# plc-6u-rs485-router.net
KiCad netlist of a schematic drawn in EAGLE
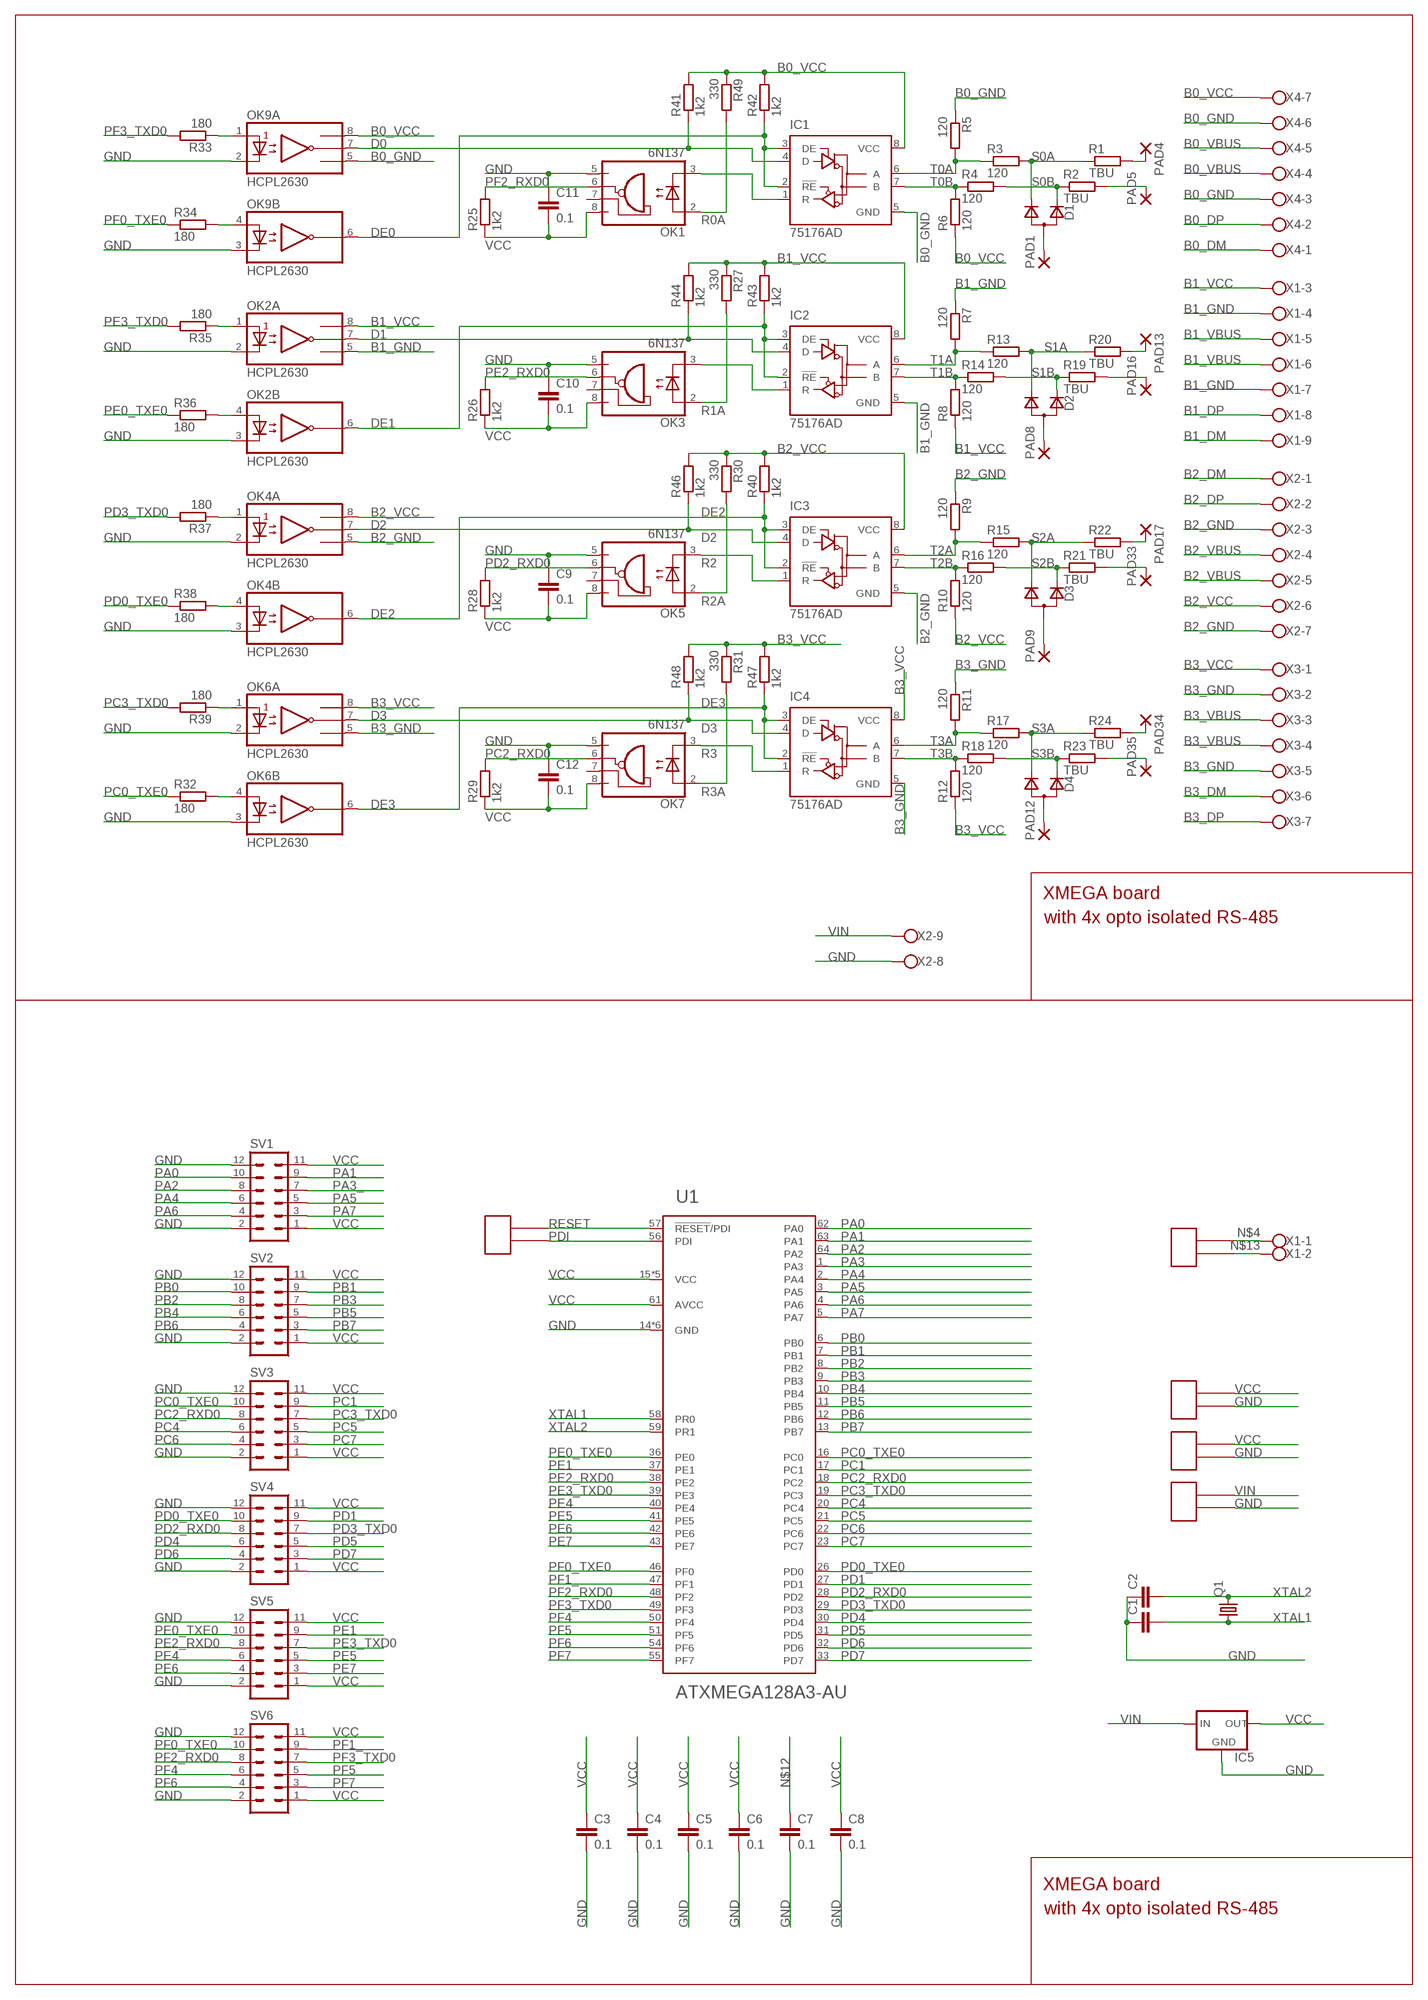
[diagram p0: schematic, sheet 1]

(export (version "E")
  (design (tool "Eeschema 10.0.6"))
  (components
    (comp (ref "C1")
      (value "C-EUC0805")
      (footprint "eagle-import:C0805")
      (libsource (lib "eagle-import") (part "C-EUC0805"))
    )
    (comp (ref "C2")
      (value "C-EUC0805")
      (footprint "eagle-import:C0805")
      (libsource (lib "eagle-import") (part "C-EUC0805"))
    )
    (comp (ref "C3")
      (value "0.1")
      (footprint "eagle-import:C0603")
      (libsource (lib "eagle-import") (part "C-EUC0603"))
    )
    (comp (ref "C4")
      (value "0.1")
      (footprint "eagle-import:C0603")
      (libsource (lib "eagle-import") (part "C-EUC0603"))
    )
    (comp (ref "C5")
      (value "0.1")
      (footprint "eagle-import:C0603")
      (libsource (lib "eagle-import") (part "C-EUC0603"))
    )
    (comp (ref "C6")
      (value "0.1")
      (footprint "eagle-import:C0603")
      (libsource (lib "eagle-import") (part "C-EUC0603"))
    )
    (comp (ref "C7")
      (value "0.1")
      (footprint "eagle-import:C0603")
      (libsource (lib "eagle-import") (part "C-EUC0603"))
    )
    (comp (ref "C8")
      (value "0.1")
      (footprint "eagle-import:C0603")
      (libsource (lib "eagle-import") (part "C-EUC0603"))
    )
    (comp (ref "C9")
      (value "0.1")
      (footprint "eagle-import:C1206")
      (libsource (lib "eagle-import") (part "C-EUC1206"))
    )
    (comp (ref "C10")
      (value "0.1")
      (footprint "eagle-import:C1206")
      (libsource (lib "eagle-import") (part "C-EUC1206"))
    )
    (comp (ref "C11")
      (value "0.1")
      (footprint "eagle-import:C1206")
      (libsource (lib "eagle-import") (part "C-EUC1206"))
    )
    (comp (ref "C12")
      (value "0.1")
      (footprint "eagle-import:C1206")
      (libsource (lib "eagle-import") (part "C-EUC1206"))
    )
    (comp (ref "D1")
      (value "D_2CSOT323")
      (footprint "eagle-import:SOT323")
      (libsource (lib "eagle-import") (part "D_2CSOT323"))
    )
    (comp (ref "D2")
      (value "D_2CSOT323")
      (footprint "eagle-import:SOT323")
      (fields (field (name "OC_FARNELL") "unknown") (field (name "OC_NEWARK") "unknown"))
      (libsource (lib "eagle-import") (part "D_2CSOT323"))
    )
    (comp (ref "D3")
      (value "D_2CSOT323")
      (footprint "eagle-import:SOT323")
      (fields (field (name "OC_FARNELL") "unknown") (field (name "OC_NEWARK") "unknown"))
      (libsource (lib "eagle-import") (part "D_2CSOT323"))
    )
    (comp (ref "D4")
      (value "D_2CSOT323")
      (footprint "eagle-import:SOT323")
      (fields (field (name "OC_FARNELL") "unknown") (field (name "OC_NEWARK") "unknown"))
      (libsource (lib "eagle-import") (part "D_2CSOT323"))
    )
    (comp (ref "IC1")
      (value "75176AD")
      (footprint "eagle-import:D_R-PDSO-G8")
      (libsource (lib "eagle-import") (part "75176AD"))
    )
    (comp (ref "IC2")
      (value "75176AD")
      (footprint "eagle-import:D_R-PDSO-G8")
      (libsource (lib "eagle-import") (part "75176AD"))
    )
    (comp (ref "IC3")
      (value "75176AD")
      (footprint "eagle-import:D_R-PDSO-G8")
      (libsource (lib "eagle-import") (part "75176AD"))
    )
    (comp (ref "IC4")
      (value "75176AD")
      (footprint "eagle-import:D_R-PDSO-G8")
      (libsource (lib "eagle-import") (part "75176AD"))
    )
    (comp (ref "IC5")
      (value "LM1117TO252")
      (footprint "eagle-import:TO252")
      (libsource (lib "eagle-import") (part "LM1117TO252"))
    )
    (comp (ref "OK1")
      (value "6N137")
      (footprint "eagle-import:DIL08")
      (libsource (lib "eagle-import") (part "6N137"))
    )
    (comp (ref "OK2")
      (value "HCPL2630")
      (footprint "eagle-import:DIL08")
      (fields (field (name "MF") "AGILENT TECHNOLOGIES") (field (name "MPN") "HCPL-2630-000E"))
      (libsource (lib "eagle-import") (part "HCPL2630"))
    )
    (comp (ref "OK3")
      (value "6N137")
      (footprint "eagle-import:DIL08")
      (libsource (lib "eagle-import") (part "6N137"))
    )
    (comp (ref "OK4")
      (value "HCPL2630")
      (footprint "eagle-import:DIL08")
      (fields (field (name "MF") "AGILENT TECHNOLOGIES") (field (name "MPN") "HCPL-2630-000E"))
      (libsource (lib "eagle-import") (part "HCPL2630"))
    )
    (comp (ref "OK5")
      (value "6N137")
      (footprint "eagle-import:DIL08")
      (libsource (lib "eagle-import") (part "6N137"))
    )
    (comp (ref "OK6")
      (value "HCPL2630")
      (footprint "eagle-import:DIL08")
      (fields (field (name "MF") "AGILENT TECHNOLOGIES") (field (name "MPN") "HCPL-2630-000E"))
      (libsource (lib "eagle-import") (part "HCPL2630"))
    )
    (comp (ref "OK7")
      (value "6N137")
      (footprint "eagle-import:DIL08")
      (libsource (lib "eagle-import") (part "6N137"))
    )
    (comp (ref "OK9")
      (value "HCPL2630")
      (footprint "eagle-import:DIL08")
      (fields (field (name "MF") "AGILENT TECHNOLOGIES") (field (name "MPN") "HCPL-2630-000E"))
      (libsource (lib "eagle-import") (part "HCPL2630"))
    )
    (comp (ref "PAD1")
      (value "2,54/0,8")
      (footprint "eagle-import:2,54_0,8")
      (libsource (lib "eagle-import") (part "2,54/0,8"))
    )
    (comp (ref "PAD4")
      (value "2,54/0,8")
      (footprint "eagle-import:2,54_0,8")
      (libsource (lib "eagle-import") (part "2,54/0,8"))
    )
    (comp (ref "PAD5")
      (value "2,54/0,8")
      (footprint "eagle-import:2,54_0,8")
      (libsource (lib "eagle-import") (part "2,54/0,8"))
    )
    (comp (ref "PAD8")
      (value "2,54/0,8")
      (footprint "eagle-import:2,54_0,8")
      (libsource (lib "eagle-import") (part "2,54/0,8"))
    )
    (comp (ref "PAD9")
      (value "2,54/0,8")
      (footprint "eagle-import:2,54_0,8")
      (libsource (lib "eagle-import") (part "2,54/0,8"))
    )
    (comp (ref "PAD12")
      (value "2,54/0,8")
      (footprint "eagle-import:2,54_0,8")
      (libsource (lib "eagle-import") (part "2,54/0,8"))
    )
    (comp (ref "PAD13")
      (value "2,54/0,8")
      (footprint "eagle-import:2,54_0,8")
      (libsource (lib "eagle-import") (part "2,54/0,8"))
    )
    (comp (ref "PAD16")
      (value "2,54/0,8")
      (footprint "eagle-import:2,54_0,8")
      (libsource (lib "eagle-import") (part "2,54/0,8"))
    )
    (comp (ref "PAD17")
      (value "2,54/0,8")
      (footprint "eagle-import:2,54_0,8")
      (libsource (lib "eagle-import") (part "2,54/0,8"))
    )
    (comp (ref "PAD33")
      (value "2,54/0,8")
      (footprint "eagle-import:2,54_0,8")
      (libsource (lib "eagle-import") (part "2,54/0,8"))
    )
    (comp (ref "PAD34")
      (value "2,54/0,8")
      (footprint "eagle-import:2,54_0,8")
      (libsource (lib "eagle-import") (part "2,54/0,8"))
    )
    (comp (ref "PAD35")
      (value "2,54/0,8")
      (footprint "eagle-import:2,54_0,8")
      (libsource (lib "eagle-import") (part "2,54/0,8"))
    )
    (comp (ref "Q1")
      (value "CRYSTALHC49S")
      (footprint "eagle-import:HC49_S")
      (libsource (lib "eagle-import") (part "CRYSTALHC49S"))
    )
    (comp (ref "R1")
      (value "TBU")
      (footprint "eagle-import:WSC2515")
      (libsource (lib "eagle-import") (part "R-EU_WSC2515"))
    )
    (comp (ref "R2")
      (value "TBU")
      (footprint "eagle-import:WSC2515")
      (libsource (lib "eagle-import") (part "R-EU_WSC2515"))
    )
    (comp (ref "R3")
      (value "120")
      (footprint "eagle-import:R0805")
      (libsource (lib "eagle-import") (part "R-EU_R0805"))
    )
    (comp (ref "R4")
      (value "120")
      (footprint "eagle-import:R0805")
      (libsource (lib "eagle-import") (part "R-EU_R0805"))
    )
    (comp (ref "R5")
      (value "120")
      (footprint "eagle-import:R0805")
      (libsource (lib "eagle-import") (part "R-EU_R0805"))
    )
    (comp (ref "R6")
      (value "120")
      (footprint "eagle-import:R0805")
      (libsource (lib "eagle-import") (part "R-EU_R0805"))
    )
    (comp (ref "R7")
      (value "120")
      (footprint "eagle-import:R0805")
      (libsource (lib "eagle-import") (part "R-EU_R0805"))
    )
    (comp (ref "R8")
      (value "120")
      (footprint "eagle-import:R0805")
      (libsource (lib "eagle-import") (part "R-EU_R0805"))
    )
    (comp (ref "R9")
      (value "120")
      (footprint "eagle-import:R0805")
      (libsource (lib "eagle-import") (part "R-EU_R0805"))
    )
    (comp (ref "R10")
      (value "120")
      (footprint "eagle-import:R0805")
      (libsource (lib "eagle-import") (part "R-EU_R0805"))
    )
    (comp (ref "R11")
      (value "120")
      (footprint "eagle-import:R0805")
      (libsource (lib "eagle-import") (part "R-EU_R0805"))
    )
    (comp (ref "R12")
      (value "120")
      (footprint "eagle-import:R0805")
      (libsource (lib "eagle-import") (part "R-EU_R0805"))
    )
    (comp (ref "R13")
      (value "120")
      (footprint "eagle-import:R0805")
      (libsource (lib "eagle-import") (part "R-EU_R0805"))
    )
    (comp (ref "R14")
      (value "120")
      (footprint "eagle-import:R0805")
      (libsource (lib "eagle-import") (part "R-EU_R0805"))
    )
    (comp (ref "R15")
      (value "120")
      (footprint "eagle-import:R0805")
      (libsource (lib "eagle-import") (part "R-EU_R0805"))
    )
    (comp (ref "R16")
      (value "120")
      (footprint "eagle-import:R0805")
      (libsource (lib "eagle-import") (part "R-EU_R0805"))
    )
    (comp (ref "R17")
      (value "120")
      (footprint "eagle-import:R0805")
      (libsource (lib "eagle-import") (part "R-EU_R0805"))
    )
    (comp (ref "R18")
      (value "120")
      (footprint "eagle-import:R0805")
      (libsource (lib "eagle-import") (part "R-EU_R0805"))
    )
    (comp (ref "R19")
      (value "TBU")
      (footprint "eagle-import:WSC2515")
      (libsource (lib "eagle-import") (part "R-EU_WSC2515"))
    )
    (comp (ref "R20")
      (value "TBU")
      (footprint "eagle-import:WSC2515")
      (libsource (lib "eagle-import") (part "R-EU_WSC2515"))
    )
    (comp (ref "R21")
      (value "TBU")
      (footprint "eagle-import:WSC2515")
      (libsource (lib "eagle-import") (part "R-EU_WSC2515"))
    )
    (comp (ref "R22")
      (value "TBU")
      (footprint "eagle-import:WSC2515")
      (libsource (lib "eagle-import") (part "R-EU_WSC2515"))
    )
    (comp (ref "R23")
      (value "TBU")
      (footprint "eagle-import:WSC2515")
      (libsource (lib "eagle-import") (part "R-EU_WSC2515"))
    )
    (comp (ref "R24")
      (value "TBU")
      (footprint "eagle-import:WSC2515")
      (libsource (lib "eagle-import") (part "R-EU_WSC2515"))
    )
    (comp (ref "R25")
      (value "1k2")
      (footprint "eagle-import:R0805")
      (libsource (lib "eagle-import") (part "R-EU_R0805"))
    )
    (comp (ref "R26")
      (value "1k2")
      (footprint "eagle-import:R0805")
      (libsource (lib "eagle-import") (part "R-EU_R0805"))
    )
    (comp (ref "R27")
      (value "330")
      (footprint "eagle-import:R0805")
      (libsource (lib "eagle-import") (part "R-EU_R0805"))
    )
    (comp (ref "R28")
      (value "1k2")
      (footprint "eagle-import:R0805")
      (libsource (lib "eagle-import") (part "R-EU_R0805"))
    )
    (comp (ref "R29")
      (value "1k2")
      (footprint "eagle-import:R0805")
      (libsource (lib "eagle-import") (part "R-EU_R0805"))
    )
    (comp (ref "R30")
      (value "330")
      (footprint "eagle-import:R0805")
      (libsource (lib "eagle-import") (part "R-EU_R0805"))
    )
    (comp (ref "R31")
      (value "330")
      (footprint "eagle-import:R0805")
      (libsource (lib "eagle-import") (part "R-EU_R0805"))
    )
    (comp (ref "R32")
      (value "180")
      (footprint "eagle-import:R1206")
      (libsource (lib "eagle-import") (part "R-EU_R1206"))
    )
    (comp (ref "R33")
      (value "180")
      (footprint "eagle-import:R0805")
      (libsource (lib "eagle-import") (part "R-EU_R0805"))
    )
    (comp (ref "R34")
      (value "180")
      (footprint "eagle-import:R1206")
      (libsource (lib "eagle-import") (part "R-EU_R1206"))
    )
    (comp (ref "R35")
      (value "180")
      (footprint "eagle-import:R0805")
      (libsource (lib "eagle-import") (part "R-EU_R0805"))
    )
    (comp (ref "R36")
      (value "180")
      (footprint "eagle-import:R1206")
      (libsource (lib "eagle-import") (part "R-EU_R1206"))
    )
    (comp (ref "R37")
      (value "180")
      (footprint "eagle-import:R0805")
      (libsource (lib "eagle-import") (part "R-EU_R0805"))
    )
    (comp (ref "R38")
      (value "180")
      (footprint "eagle-import:R1206")
      (libsource (lib "eagle-import") (part "R-EU_R1206"))
    )
    (comp (ref "R39")
      (value "180")
      (footprint "eagle-import:R0805")
      (libsource (lib "eagle-import") (part "R-EU_R0805"))
    )
    (comp (ref "R40")
      (value "1k2")
      (footprint "eagle-import:0207_10")
      (libsource (lib "eagle-import") (part "resistor_R-EU_0207/10"))
    )
    (comp (ref "R41")
      (value "1k2")
      (footprint "eagle-import:0207_10")
      (libsource (lib "eagle-import") (part "resistor_R-EU_0207/10"))
    )
    (comp (ref "R42")
      (value "1k2")
      (footprint "eagle-import:0207_10")
      (libsource (lib "eagle-import") (part "resistor_R-EU_0207/10"))
    )
    (comp (ref "R43")
      (value "1k2")
      (footprint "eagle-import:R0805")
      (libsource (lib "eagle-import") (part "R-EU_R0805"))
    )
    (comp (ref "R44")
      (value "1k2")
      (footprint "eagle-import:R0805")
      (libsource (lib "eagle-import") (part "R-EU_R0805"))
    )
    (comp (ref "R46")
      (value "1k2")
      (footprint "eagle-import:0207_10")
      (libsource (lib "eagle-import") (part "resistor_R-EU_0207/10"))
    )
    (comp (ref "R47")
      (value "1k2")
      (footprint "eagle-import:R0805")
      (libsource (lib "eagle-import") (part "R-EU_R0805"))
    )
    (comp (ref "R48")
      (value "1k2")
      (footprint "eagle-import:R0805")
      (libsource (lib "eagle-import") (part "R-EU_R0805"))
    )
    (comp (ref "R49")
      (value "330")
      (footprint "eagle-import:R0805")
      (libsource (lib "eagle-import") (part "R-EU_R0805"))
    )
    (comp (ref "SV1")
      (value "MA06-2")
      (footprint "eagle-import:MA06-2")
      (libsource (lib "eagle-import") (part "MA06-2"))
    )
    (comp (ref "SV2")
      (value "MA06-2")
      (footprint "eagle-import:MA06-2")
      (libsource (lib "eagle-import") (part "MA06-2"))
    )
    (comp (ref "SV3")
      (value "MA06-2")
      (footprint "eagle-import:MA06-2")
      (libsource (lib "eagle-import") (part "MA06-2"))
    )
    (comp (ref "SV4")
      (value "MA06-2")
      (footprint "eagle-import:MA06-2")
      (libsource (lib "eagle-import") (part "MA06-2"))
    )
    (comp (ref "SV5")
      (value "MA06-2")
      (footprint "eagle-import:MA06-2")
      (libsource (lib "eagle-import") (part "MA06-2"))
    )
    (comp (ref "SV6")
      (value "MA06-2")
      (footprint "eagle-import:MA06-2")
      (libsource (lib "eagle-import") (part "MA06-2"))
    )
    (comp (ref "U$1")
      (value "MA02-1")
      (footprint "eagle-import:MA02-1")
      (libsource (lib "eagle-import") (part "MA02-1"))
    )
    (comp (ref "U$2")
      (value "MA02-1")
      (footprint "eagle-import:MA02-1")
      (libsource (lib "eagle-import") (part "MA02-1"))
    )
    (comp (ref "U$3")
      (value "MA02-1")
      (footprint "eagle-import:MA02-1")
      (libsource (lib "eagle-import") (part "MA02-1"))
    )
    (comp (ref "U$4")
      (value "MA02-1")
      (footprint "eagle-import:MA02-1")
      (libsource (lib "eagle-import") (part "MA02-1"))
    )
    (comp (ref "U$5")
      (value "MA02-1")
      (footprint "eagle-import:MA02-1")
      (libsource (lib "eagle-import") (part "MA02-1"))
    )
    (comp (ref "U1")
      (value "ATXMEGA128A3-AU")
      (footprint "eagle-import:TQFP-64A-64")
      (libsource (lib "eagle-import") (part "ATXMEGA128A3-AU"))
    )
    (comp (ref "X1")
      (value "W237-09P")
      (footprint "eagle-import:W237-9P")
      (libsource (lib "eagle-import") (part "W237-09P"))
    )
    (comp (ref "X2")
      (value "W237-09P")
      (footprint "eagle-import:W237-9P")
      (libsource (lib "eagle-import") (part "W237-09P"))
    )
    (comp (ref "X3")
      (value "W237-07P")
      (footprint "eagle-import:W237-7P")
      (libsource (lib "eagle-import") (part "W237-07P"))
    )
    (comp (ref "X4")
      (value "W237-07P")
      (footprint "eagle-import:W237-7P")
      (libsource (lib "eagle-import") (part "W237-07P"))
    )
  )
  (nets
    (net (code "1") (name "/B0_DM") (class "Default")
      (node (ref "PAD4") (pin "1") (pinfunction "P_1") (pintype "passive"))
      (node (ref "R1") (pin "2") (pinfunction "2_2") (pintype "passive"))
      (node (ref "X4") (pin "1") (pinfunction "KL_1") (pintype "passive"))
    )
    (net (code "2") (name "/B0_DP") (class "Default")
      (node (ref "PAD5") (pin "1") (pinfunction "P_1") (pintype "passive"))
      (node (ref "R2") (pin "2") (pinfunction "2_2") (pintype "passive"))
      (node (ref "X4") (pin "2") (pinfunction "KL_2") (pintype "passive"))
    )
    (net (code "3") (name "/B0_GND") (class "Default")
      (node (ref "D1") (pin "1") (pinfunction "A_1") (pintype "passive"))
      (node (ref "IC1") (pin "5") (pinfunction "GND_5") (pintype "power_in"))
      (node (ref "OK9") (pin "5") (pinfunction "GND_5") (pintype "passive"))
      (node (ref "PAD1") (pin "1") (pinfunction "P_1") (pintype "passive"))
      (node (ref "R5") (pin "1") (pinfunction "1_1") (pintype "passive"))
      (node (ref "X4") (pin "3") (pinfunction "KL_3") (pintype "passive"))
      (node (ref "X4") (pin "6") (pinfunction "KL_6") (pintype "passive"))
    )
    (net (code "4") (name "/B0_VBUS") (class "Default")
      (node (ref "X4") (pin "4") (pinfunction "KL_4") (pintype "passive"))
      (node (ref "X4") (pin "5") (pinfunction "KL_5") (pintype "passive"))
    )
    (net (code "5") (name "/B0_VCC") (class "Default")
      (node (ref "IC1") (pin "8") (pinfunction "VCC_8") (pintype "power_in"))
      (node (ref "OK9") (pin "8") (pinfunction "VCC_8") (pintype "passive"))
      (node (ref "R41") (pin "2") (pinfunction "2_2") (pintype "passive"))
      (node (ref "R42") (pin "2") (pinfunction "2_2") (pintype "passive"))
      (node (ref "R49") (pin "1") (pinfunction "1_1") (pintype "passive"))
      (node (ref "R6") (pin "1") (pinfunction "1_1") (pintype "passive"))
      (node (ref "X4") (pin "7") (pinfunction "KL_7") (pintype "passive"))
    )
    (net (code "6") (name "/B1_DM") (class "Default")
      (node (ref "PAD16") (pin "1") (pinfunction "P_1") (pintype "passive"))
      (node (ref "R19") (pin "2") (pinfunction "2_2") (pintype "passive"))
      (node (ref "X1") (pin "9") (pinfunction "KL_9") (pintype "passive"))
    )
    (net (code "7") (name "/B1_DP") (class "Default")
      (node (ref "PAD13") (pin "1") (pinfunction "P_1") (pintype "passive"))
      (node (ref "R20") (pin "2") (pinfunction "2_2") (pintype "passive"))
      (node (ref "X1") (pin "8") (pinfunction "KL_8") (pintype "passive"))
    )
    (net (code "8") (name "/B1_GND") (class "Default")
      (node (ref "D2") (pin "1") (pinfunction "A_1") (pintype "passive"))
      (node (ref "IC2") (pin "5") (pinfunction "GND_5") (pintype "power_in"))
      (node (ref "OK2") (pin "5") (pinfunction "GND_5") (pintype "passive"))
      (node (ref "PAD8") (pin "1") (pinfunction "P_1") (pintype "passive"))
      (node (ref "R7") (pin "1") (pinfunction "1_1") (pintype "passive"))
      (node (ref "X1") (pin "4") (pinfunction "KL_4") (pintype "passive"))
      (node (ref "X1") (pin "7") (pinfunction "KL_7") (pintype "passive"))
    )
    (net (code "9") (name "/B1_VBUS") (class "Default")
      (node (ref "X1") (pin "5") (pinfunction "KL_5") (pintype "passive"))
      (node (ref "X1") (pin "6") (pinfunction "KL_6") (pintype "passive"))
    )
    (net (code "10") (name "/B1_VCC") (class "Default")
      (node (ref "IC2") (pin "8") (pinfunction "VCC_8") (pintype "power_in"))
      (node (ref "OK2") (pin "8") (pinfunction "VCC_8") (pintype "passive"))
      (node (ref "R27") (pin "1") (pinfunction "1_1") (pintype "passive"))
      (node (ref "R43") (pin "2") (pinfunction "2_2") (pintype "passive"))
      (node (ref "R44") (pin "2") (pinfunction "2_2") (pintype "passive"))
      (node (ref "R8") (pin "1") (pinfunction "1_1") (pintype "passive"))
      (node (ref "X1") (pin "3") (pinfunction "KL_3") (pintype "passive"))
    )
    (net (code "11") (name "/B2_DM") (class "Default")
      (node (ref "PAD17") (pin "1") (pinfunction "P_1") (pintype "passive"))
      (node (ref "R22") (pin "2") (pinfunction "2_2") (pintype "passive"))
      (node (ref "X2") (pin "1") (pinfunction "KL_1") (pintype "passive"))
    )
    (net (code "12") (name "/B2_DP") (class "Default")
      (node (ref "PAD33") (pin "1") (pinfunction "P_1") (pintype "passive"))
      (node (ref "R21") (pin "2") (pinfunction "2_2") (pintype "passive"))
      (node (ref "X2") (pin "2") (pinfunction "KL_2") (pintype "passive"))
    )
    (net (code "13") (name "/B2_GND") (class "Default")
      (node (ref "D3") (pin "1") (pinfunction "A_1") (pintype "passive"))
      (node (ref "IC3") (pin "5") (pinfunction "GND_5") (pintype "power_in"))
      (node (ref "OK4") (pin "5") (pinfunction "GND_5") (pintype "passive"))
      (node (ref "PAD9") (pin "1") (pinfunction "P_1") (pintype "passive"))
      (node (ref "R9") (pin "1") (pinfunction "1_1") (pintype "passive"))
      (node (ref "X2") (pin "3") (pinfunction "KL_3") (pintype "passive"))
      (node (ref "X2") (pin "7") (pinfunction "KL_7") (pintype "passive"))
    )
    (net (code "14") (name "/B2_VBUS") (class "Default")
      (node (ref "X2") (pin "4") (pinfunction "KL_4") (pintype "passive"))
      (node (ref "X2") (pin "5") (pinfunction "KL_5") (pintype "passive"))
    )
    (net (code "15") (name "/B2_VCC") (class "Default")
      (node (ref "IC3") (pin "8") (pinfunction "VCC_8") (pintype "power_in"))
      (node (ref "OK4") (pin "8") (pinfunction "VCC_8") (pintype "passive"))
      (node (ref "R10") (pin "1") (pinfunction "1_1") (pintype "passive"))
      (node (ref "R30") (pin "1") (pinfunction "1_1") (pintype "passive"))
      (node (ref "R40") (pin "2") (pinfunction "2_2") (pintype "passive"))
      (node (ref "R46") (pin "2") (pinfunction "2_2") (pintype "passive"))
      (node (ref "X2") (pin "6") (pinfunction "KL_6") (pintype "passive"))
    )
    (net (code "16") (name "/B3_DM") (class "Default")
      (node (ref "PAD34") (pin "1") (pinfunction "P_1") (pintype "passive"))
      (node (ref "R24") (pin "2") (pinfunction "2_2") (pintype "passive"))
      (node (ref "X3") (pin "6") (pinfunction "KL_6") (pintype "passive"))
    )
    (net (code "17") (name "/B3_DP") (class "Default")
      (node (ref "PAD35") (pin "1") (pinfunction "P_1") (pintype "passive"))
      (node (ref "R23") (pin "2") (pinfunction "2_2") (pintype "passive"))
      (node (ref "X3") (pin "7") (pinfunction "KL_7") (pintype "passive"))
    )
    (net (code "18") (name "/B3_GND") (class "Default")
      (node (ref "D4") (pin "1") (pinfunction "A_1") (pintype "passive"))
      (node (ref "IC4") (pin "5") (pinfunction "GND_5") (pintype "power_in"))
      (node (ref "OK6") (pin "5") (pinfunction "GND_5") (pintype "passive"))
      (node (ref "PAD12") (pin "1") (pinfunction "P_1") (pintype "passive"))
      (node (ref "R11") (pin "1") (pinfunction "1_1") (pintype "passive"))
      (node (ref "X3") (pin "2") (pinfunction "KL_2") (pintype "passive"))
      (node (ref "X3") (pin "5") (pinfunction "KL_5") (pintype "passive"))
    )
    (net (code "19") (name "/B3_VBUS") (class "Default")
      (node (ref "X3") (pin "3") (pinfunction "KL_3") (pintype "passive"))
      (node (ref "X3") (pin "4") (pinfunction "KL_4") (pintype "passive"))
    )
    (net (code "20") (name "/B3_VCC") (class "Default")
      (node (ref "IC4") (pin "8") (pinfunction "VCC_8") (pintype "power_in"))
      (node (ref "OK6") (pin "8") (pinfunction "VCC_8") (pintype "passive"))
      (node (ref "R12") (pin "1") (pinfunction "1_1") (pintype "passive"))
      (node (ref "R31") (pin "1") (pinfunction "1_1") (pintype "passive"))
      (node (ref "R47") (pin "2") (pinfunction "2_2") (pintype "passive"))
      (node (ref "R48") (pin "2") (pinfunction "2_2") (pintype "passive"))
      (node (ref "X3") (pin "1") (pinfunction "KL_1") (pintype "passive"))
    )
    (net (code "21") (name "/D0") (class "Default")
      (node (ref "IC1") (pin "4") (pinfunction "D_4") (pintype "input"))
      (node (ref "OK9") (pin "7") (pinfunction "VO1_7") (pintype "passive"))
      (node (ref "R41") (pin "1") (pinfunction "1_1") (pintype "passive"))
    )
    (net (code "22") (name "/D1") (class "Default")
      (node (ref "IC2") (pin "4") (pinfunction "D_4") (pintype "input"))
      (node (ref "OK2") (pin "7") (pinfunction "VO1_7") (pintype "passive"))
      (node (ref "R44") (pin "1") (pinfunction "1_1") (pintype "passive"))
    )
    (net (code "23") (name "/D2") (class "Default")
      (node (ref "IC3") (pin "4") (pinfunction "D_4") (pintype "input"))
      (node (ref "OK4") (pin "7") (pinfunction "VO1_7") (pintype "passive"))
      (node (ref "R46") (pin "1") (pinfunction "1_1") (pintype "passive"))
    )
    (net (code "24") (name "/D3") (class "Default")
      (node (ref "IC4") (pin "4") (pinfunction "D_4") (pintype "input"))
      (node (ref "OK6") (pin "7") (pinfunction "VO1_7") (pintype "passive"))
      (node (ref "R48") (pin "1") (pinfunction "1_1") (pintype "passive"))
    )
    (net (code "25") (name "/DE0") (class "Default")
      (node (ref "IC1") (pin "2") (pinfunction "~{RE}_2") (pintype "input"))
      (node (ref "IC1") (pin "3") (pinfunction "DE_3") (pintype "input"))
      (node (ref "OK9") (pin "6") (pinfunction "VO2_6") (pintype "passive"))
      (node (ref "R42") (pin "1") (pinfunction "1_1") (pintype "passive"))
    )
    (net (code "26") (name "/DE1") (class "Default")
      (node (ref "IC2") (pin "2") (pinfunction "~{RE}_2") (pintype "input"))
      (node (ref "IC2") (pin "3") (pinfunction "DE_3") (pintype "input"))
      (node (ref "OK2") (pin "6") (pinfunction "VO2_6") (pintype "passive"))
      (node (ref "R43") (pin "1") (pinfunction "1_1") (pintype "passive"))
    )
    (net (code "27") (name "/DE2") (class "Default")
      (node (ref "IC3") (pin "2") (pinfunction "~{RE}_2") (pintype "input"))
      (node (ref "IC3") (pin "3") (pinfunction "DE_3") (pintype "input"))
      (node (ref "OK4") (pin "6") (pinfunction "VO2_6") (pintype "passive"))
      (node (ref "R40") (pin "1") (pinfunction "1_1") (pintype "passive"))
    )
    (net (code "28") (name "/DE3") (class "Default")
      (node (ref "IC4") (pin "2") (pinfunction "~{RE}_2") (pintype "input"))
      (node (ref "IC4") (pin "3") (pinfunction "DE_3") (pintype "input"))
      (node (ref "OK6") (pin "6") (pinfunction "VO2_6") (pintype "passive"))
      (node (ref "R47") (pin "1") (pinfunction "1_1") (pintype "passive"))
    )
    (net (code "29") (name "/GND") (class "Default")
      (node (ref "C1") (pin "1") (pinfunction "1_1") (pintype "passive"))
      (node (ref "C10") (pin "1") (pinfunction "1_1") (pintype "passive"))
      (node (ref "C11") (pin "1") (pinfunction "1_1") (pintype "passive"))
      (node (ref "C12") (pin "1") (pinfunction "1_1") (pintype "passive"))
      (node (ref "C2") (pin "1") (pinfunction "1_1") (pintype "passive"))
      (node (ref "C3") (pin "2") (pinfunction "2_2") (pintype "passive"))
      (node (ref "C4") (pin "2") (pinfunction "2_2") (pintype "passive"))
      (node (ref "C5") (pin "2") (pinfunction "2_2") (pintype "passive"))
      (node (ref "C6") (pin "2") (pinfunction "2_2") (pintype "passive"))
      (node (ref "C7") (pin "2") (pinfunction "2_2") (pintype "passive"))
      (node (ref "C8") (pin "2") (pinfunction "2_2") (pintype "passive"))
      (node (ref "C9") (pin "1") (pinfunction "1_1") (pintype "passive"))
      (node (ref "IC5") (pin "1") (pinfunction "GND_1") (pintype "input"))
      (node (ref "OK1") (pin "5") (pinfunction "GND_5") (pintype "passive"))
      (node (ref "OK2") (pin "2") (pinfunction "C1_2") (pintype "passive"))
      (node (ref "OK2") (pin "3") (pinfunction "C2_3") (pintype "passive"))
      (node (ref "OK3") (pin "5") (pinfunction "GND_5") (pintype "passive"))
      (node (ref "OK4") (pin "2") (pinfunction "C1_2") (pintype "passive"))
      (node (ref "OK4") (pin "3") (pinfunction "C2_3") (pintype "passive"))
      (node (ref "OK5") (pin "5") (pinfunction "GND_5") (pintype "passive"))
      (node (ref "OK6") (pin "2") (pinfunction "C1_2") (pintype "passive"))
      (node (ref "OK6") (pin "3") (pinfunction "C2_3") (pintype "passive"))
      (node (ref "OK7") (pin "5") (pinfunction "GND_5") (pintype "passive"))
      (node (ref "OK9") (pin "2") (pinfunction "C1_2") (pintype "passive"))
      (node (ref "OK9") (pin "3") (pinfunction "C2_3") (pintype "passive"))
      (node (ref "SV1") (pin "12") (pinfunction "12_12") (pintype "passive"))
      (node (ref "SV1") (pin "2") (pinfunction "2_2") (pintype "passive"))
      (node (ref "SV2") (pin "12") (pinfunction "12_12") (pintype "passive"))
      (node (ref "SV2") (pin "2") (pinfunction "2_2") (pintype "passive"))
      (node (ref "SV3") (pin "12") (pinfunction "12_12") (pintype "passive"))
      (node (ref "SV3") (pin "2") (pinfunction "2_2") (pintype "passive"))
      (node (ref "SV4") (pin "12") (pinfunction "12_12") (pintype "passive"))
      (node (ref "SV4") (pin "2") (pinfunction "2_2") (pintype "passive"))
      (node (ref "SV5") (pin "12") (pinfunction "12_12") (pintype "passive"))
      (node (ref "SV5") (pin "2") (pinfunction "2_2") (pintype "passive"))
      (node (ref "SV6") (pin "12") (pinfunction "12_12") (pintype "passive"))
      (node (ref "SV6") (pin "2") (pinfunction "2_2") (pintype "passive"))
      (node (ref "U$2") (pin "P1") (pinfunction "P1_P1") (pintype "bidirectional"))
      (node (ref "U$3") (pin "P1") (pinfunction "P1_P1") (pintype "bidirectional"))
      (node (ref "U$4") (pin "P1") (pinfunction "P1_P1") (pintype "bidirectional"))
      (node (ref "U1") (pin "14") (pinfunction "GND_14") (pintype "power_in"))
      (node (ref "U1") (pin "24") (pinfunction "GND_24") (pintype "power_in"))
      (node (ref "U1") (pin "34") (pinfunction "GND_34") (pintype "power_in"))
      (node (ref "U1") (pin "44") (pinfunction "GND_44") (pintype "power_in"))
      (node (ref "U1") (pin "52") (pinfunction "GND_52") (pintype "power_in"))
      (node (ref "U1") (pin "60") (pinfunction "GND_60") (pintype "power_in"))
      (node (ref "X2") (pin "8") (pinfunction "KL_8") (pintype "passive"))
    )
    (net (code "30") (name "/N$4") (class "Default")
      (node (ref "U$5") (pin "P2") (pinfunction "P2_P2") (pintype "bidirectional"))
      (node (ref "X1") (pin "1") (pinfunction "KL_1") (pintype "passive"))
    )
    (net (code "31") (name "/N$12") (class "Default")
      (node (ref "C7") (pin "1") (pinfunction "1_1") (pintype "passive"))
    )
    (net (code "32") (name "/N$13") (class "Default")
      (node (ref "U$5") (pin "P1") (pinfunction "P1_P1") (pintype "bidirectional"))
      (node (ref "X1") (pin "2") (pinfunction "KL_2") (pintype "passive"))
    )
    (net (code "33") (name "/PA0") (class "Default")
      (node (ref "SV1") (pin "10") (pinfunction "10_10") (pintype "passive"))
      (node (ref "U1") (pin "62") (pinfunction "PA0_62") (pintype "bidirectional"))
    )
    (net (code "34") (name "/PA1") (class "Default")
      (node (ref "SV1") (pin "9") (pinfunction "9_9") (pintype "passive"))
      (node (ref "U1") (pin "63") (pinfunction "PA1_63") (pintype "bidirectional"))
    )
    (net (code "35") (name "/PA2") (class "Default")
      (node (ref "SV1") (pin "8") (pinfunction "8_8") (pintype "passive"))
      (node (ref "U1") (pin "64") (pinfunction "PA2_64") (pintype "bidirectional"))
    )
    (net (code "36") (name "/PA3") (class "Default")
      (node (ref "U1") (pin "1") (pinfunction "PA3_1") (pintype "bidirectional"))
    )
    (net (code "37") (name "/PA3_") (class "Default")
      (node (ref "SV1") (pin "7") (pinfunction "7_7") (pintype "passive"))
    )
    (net (code "38") (name "/PA4") (class "Default")
      (node (ref "SV1") (pin "6") (pinfunction "6_6") (pintype "passive"))
      (node (ref "U1") (pin "2") (pinfunction "PA4_2") (pintype "bidirectional"))
    )
    (net (code "39") (name "/PA5") (class "Default")
      (node (ref "SV1") (pin "5") (pinfunction "5_5") (pintype "passive"))
      (node (ref "U1") (pin "3") (pinfunction "PA5_3") (pintype "bidirectional"))
    )
    (net (code "40") (name "/PA6") (class "Default")
      (node (ref "SV1") (pin "4") (pinfunction "4_4") (pintype "passive"))
      (node (ref "U1") (pin "4") (pinfunction "PA6_4") (pintype "bidirectional"))
    )
    (net (code "41") (name "/PA7") (class "Default")
      (node (ref "SV1") (pin "3") (pinfunction "3_3") (pintype "passive"))
      (node (ref "U1") (pin "5") (pinfunction "PA7_5") (pintype "bidirectional"))
    )
    (net (code "42") (name "/PB0") (class "Default")
      (node (ref "SV2") (pin "10") (pinfunction "10_10") (pintype "passive"))
      (node (ref "U1") (pin "6") (pinfunction "PB0_6") (pintype "bidirectional"))
    )
    (net (code "43") (name "/PB1") (class "Default")
      (node (ref "SV2") (pin "9") (pinfunction "9_9") (pintype "passive"))
      (node (ref "U1") (pin "7") (pinfunction "PB1_7") (pintype "bidirectional"))
    )
    (net (code "44") (name "/PB2") (class "Default")
      (node (ref "SV2") (pin "8") (pinfunction "8_8") (pintype "passive"))
      (node (ref "U1") (pin "8") (pinfunction "PB2_8") (pintype "bidirectional"))
    )
    (net (code "45") (name "/PB3") (class "Default")
      (node (ref "SV2") (pin "7") (pinfunction "7_7") (pintype "passive"))
      (node (ref "U1") (pin "9") (pinfunction "PB3_9") (pintype "bidirectional"))
    )
    (net (code "46") (name "/PB4") (class "Default")
      (node (ref "SV2") (pin "6") (pinfunction "6_6") (pintype "passive"))
      (node (ref "U1") (pin "10") (pinfunction "PB4_10") (pintype "bidirectional"))
    )
    (net (code "47") (name "/PB5") (class "Default")
      (node (ref "SV2") (pin "5") (pinfunction "5_5") (pintype "passive"))
      (node (ref "U1") (pin "11") (pinfunction "PB5_11") (pintype "bidirectional"))
    )
    (net (code "48") (name "/PB6") (class "Default")
      (node (ref "SV2") (pin "4") (pinfunction "4_4") (pintype "passive"))
      (node (ref "U1") (pin "12") (pinfunction "PB6_12") (pintype "bidirectional"))
    )
    (net (code "49") (name "/PB7") (class "Default")
      (node (ref "SV2") (pin "3") (pinfunction "3_3") (pintype "passive"))
      (node (ref "U1") (pin "13") (pinfunction "PB7_13") (pintype "bidirectional"))
    )
    (net (code "50") (name "/PC0_TXE0") (class "Default")
      (node (ref "R32") (pin "1") (pinfunction "1_1") (pintype "passive"))
      (node (ref "SV3") (pin "10") (pinfunction "10_10") (pintype "passive"))
      (node (ref "U1") (pin "16") (pinfunction "PC0_16") (pintype "bidirectional"))
    )
    (net (code "51") (name "/PC1") (class "Default")
      (node (ref "SV3") (pin "9") (pinfunction "9_9") (pintype "passive"))
      (node (ref "U1") (pin "17") (pinfunction "PC1_17") (pintype "bidirectional"))
    )
    (net (code "52") (name "/PC2_RXD0") (class "Default")
      (node (ref "OK7") (pin "6") (pinfunction "VO_6") (pintype "passive"))
      (node (ref "R29") (pin "2") (pinfunction "2_2") (pintype "passive"))
      (node (ref "SV3") (pin "8") (pinfunction "8_8") (pintype "passive"))
      (node (ref "U1") (pin "18") (pinfunction "PC2_18") (pintype "bidirectional"))
    )
    (net (code "53") (name "/PC3_TXD0") (class "Default")
      (node (ref "R39") (pin "2") (pinfunction "2_2") (pintype "passive"))
      (node (ref "SV3") (pin "7") (pinfunction "7_7") (pintype "passive"))
      (node (ref "U1") (pin "19") (pinfunction "PC3_19") (pintype "bidirectional"))
    )
    (net (code "54") (name "/PC4") (class "Default")
      (node (ref "SV3") (pin "6") (pinfunction "6_6") (pintype "passive"))
      (node (ref "U1") (pin "20") (pinfunction "PC4_20") (pintype "bidirectional"))
    )
    (net (code "55") (name "/PC5") (class "Default")
      (node (ref "SV3") (pin "5") (pinfunction "5_5") (pintype "passive"))
      (node (ref "U1") (pin "21") (pinfunction "PC5_21") (pintype "bidirectional"))
    )
    (net (code "56") (name "/PC6") (class "Default")
      (node (ref "SV3") (pin "4") (pinfunction "4_4") (pintype "passive"))
      (node (ref "U1") (pin "22") (pinfunction "PC6_22") (pintype "bidirectional"))
    )
    (net (code "57") (name "/PC7") (class "Default")
      (node (ref "SV3") (pin "3") (pinfunction "3_3") (pintype "passive"))
      (node (ref "U1") (pin "23") (pinfunction "PC7_23") (pintype "bidirectional"))
    )
    (net (code "58") (name "/PD0_TXE0") (class "Default")
      (node (ref "R38") (pin "1") (pinfunction "1_1") (pintype "passive"))
      (node (ref "SV4") (pin "10") (pinfunction "10_10") (pintype "passive"))
      (node (ref "U1") (pin "26") (pinfunction "PD0_26") (pintype "bidirectional"))
    )
    (net (code "59") (name "/PD1") (class "Default")
      (node (ref "SV4") (pin "9") (pinfunction "9_9") (pintype "passive"))
      (node (ref "U1") (pin "27") (pinfunction "PD1_27") (pintype "bidirectional"))
    )
    (net (code "60") (name "/PD2_RXD0") (class "Default")
      (node (ref "OK5") (pin "6") (pinfunction "VO_6") (pintype "passive"))
      (node (ref "R28") (pin "2") (pinfunction "2_2") (pintype "passive"))
      (node (ref "SV4") (pin "8") (pinfunction "8_8") (pintype "passive"))
      (node (ref "U1") (pin "28") (pinfunction "PD2_28") (pintype "bidirectional"))
    )
    (net (code "61") (name "/PD3_TXD0") (class "Default")
      (node (ref "R37") (pin "2") (pinfunction "2_2") (pintype "passive"))
      (node (ref "SV4") (pin "7") (pinfunction "7_7") (pintype "passive"))
      (node (ref "U1") (pin "29") (pinfunction "PD3_29") (pintype "bidirectional"))
    )
    (net (code "62") (name "/PD4") (class "Default")
      (node (ref "SV4") (pin "6") (pinfunction "6_6") (pintype "passive"))
      (node (ref "U1") (pin "30") (pinfunction "PD4_30") (pintype "bidirectional"))
    )
    (net (code "63") (name "/PD5") (class "Default")
      (node (ref "SV4") (pin "5") (pinfunction "5_5") (pintype "passive"))
      (node (ref "U1") (pin "31") (pinfunction "PD5_31") (pintype "bidirectional"))
    )
    (net (code "64") (name "/PD6") (class "Default")
      (node (ref "SV4") (pin "4") (pinfunction "4_4") (pintype "passive"))
      (node (ref "U1") (pin "32") (pinfunction "PD6_32") (pintype "bidirectional"))
    )
    (net (code "65") (name "/PD7") (class "Default")
      (node (ref "SV4") (pin "3") (pinfunction "3_3") (pintype "passive"))
      (node (ref "U1") (pin "33") (pinfunction "PD7_33") (pintype "bidirectional"))
    )
    (net (code "66") (name "/PDI") (class "Default")
      (node (ref "U$1") (pin "P1") (pinfunction "P1_P1") (pintype "bidirectional"))
      (node (ref "U1") (pin "56") (pinfunction "PDI_56") (pintype "bidirectional"))
    )
    (net (code "67") (name "/PE0_TXE0") (class "Default")
      (node (ref "R36") (pin "1") (pinfunction "1_1") (pintype "passive"))
      (node (ref "SV5") (pin "10") (pinfunction "10_10") (pintype "passive"))
      (node (ref "U1") (pin "36") (pinfunction "PE0_36") (pintype "bidirectional"))
    )
    (net (code "68") (name "/PE1") (class "Default")
      (node (ref "SV5") (pin "9") (pinfunction "9_9") (pintype "passive"))
      (node (ref "U1") (pin "37") (pinfunction "PE1_37") (pintype "bidirectional"))
    )
    (net (code "69") (name "/PE2_RXD0") (class "Default")
      (node (ref "OK3") (pin "6") (pinfunction "VO_6") (pintype "passive"))
      (node (ref "R26") (pin "2") (pinfunction "2_2") (pintype "passive"))
      (node (ref "SV5") (pin "8") (pinfunction "8_8") (pintype "passive"))
      (node (ref "U1") (pin "38") (pinfunction "PE2_38") (pintype "bidirectional"))
    )
    (net (code "70") (name "/PE3_TXD0") (class "Default")
      (node (ref "R35") (pin "2") (pinfunction "2_2") (pintype "passive"))
      (node (ref "SV5") (pin "7") (pinfunction "7_7") (pintype "passive"))
      (node (ref "U1") (pin "39") (pinfunction "PE3_39") (pintype "bidirectional"))
    )
    (net (code "71") (name "/PE4") (class "Default")
      (node (ref "SV5") (pin "6") (pinfunction "6_6") (pintype "passive"))
      (node (ref "U1") (pin "40") (pinfunction "PE4_40") (pintype "bidirectional"))
    )
    (net (code "72") (name "/PE5") (class "Default")
      (node (ref "SV5") (pin "5") (pinfunction "5_5") (pintype "passive"))
      (node (ref "U1") (pin "41") (pinfunction "PE5_41") (pintype "bidirectional"))
    )
    (net (code "73") (name "/PE6") (class "Default")
      (node (ref "SV5") (pin "4") (pinfunction "4_4") (pintype "passive"))
      (node (ref "U1") (pin "42") (pinfunction "PE6_42") (pintype "bidirectional"))
    )
    (net (code "74") (name "/PE7") (class "Default")
      (node (ref "SV5") (pin "3") (pinfunction "3_3") (pintype "passive"))
      (node (ref "U1") (pin "43") (pinfunction "PE7_43") (pintype "bidirectional"))
    )
    (net (code "75") (name "/PF0_TXE0") (class "Default")
      (node (ref "R34") (pin "1") (pinfunction "1_1") (pintype "passive"))
      (node (ref "SV6") (pin "10") (pinfunction "10_10") (pintype "passive"))
      (node (ref "U1") (pin "46") (pinfunction "PF0_46") (pintype "bidirectional"))
    )
    (net (code "76") (name "/PF1_") (class "Default")
      (node (ref "SV6") (pin "9") (pinfunction "9_9") (pintype "passive"))
      (node (ref "U1") (pin "47") (pinfunction "PF1_47") (pintype "bidirectional"))
    )
    (net (code "77") (name "/PF2_RXD0") (class "Default")
      (node (ref "OK1") (pin "6") (pinfunction "VO_6") (pintype "passive"))
      (node (ref "R25") (pin "2") (pinfunction "2_2") (pintype "passive"))
      (node (ref "SV6") (pin "8") (pinfunction "8_8") (pintype "passive"))
      (node (ref "U1") (pin "48") (pinfunction "PF2_48") (pintype "bidirectional"))
    )
    (net (code "78") (name "/PF3_TXD0") (class "Default")
      (node (ref "R33") (pin "2") (pinfunction "2_2") (pintype "passive"))
      (node (ref "SV6") (pin "7") (pinfunction "7_7") (pintype "passive"))
      (node (ref "U1") (pin "49") (pinfunction "PF3_49") (pintype "bidirectional"))
    )
    (net (code "79") (name "/PF4") (class "Default")
      (node (ref "SV6") (pin "6") (pinfunction "6_6") (pintype "passive"))
      (node (ref "U1") (pin "50") (pinfunction "PF4_50") (pintype "bidirectional"))
    )
    (net (code "80") (name "/PF5") (class "Default")
      (node (ref "SV6") (pin "5") (pinfunction "5_5") (pintype "passive"))
      (node (ref "U1") (pin "51") (pinfunction "PF5_51") (pintype "bidirectional"))
    )
    (net (code "81") (name "/PF6") (class "Default")
      (node (ref "SV6") (pin "4") (pinfunction "4_4") (pintype "passive"))
      (node (ref "U1") (pin "54") (pinfunction "PF6_54") (pintype "bidirectional"))
    )
    (net (code "82") (name "/PF7") (class "Default")
      (node (ref "SV6") (pin "3") (pinfunction "3_3") (pintype "passive"))
      (node (ref "U1") (pin "55") (pinfunction "PF7_55") (pintype "bidirectional"))
    )
    (net (code "83") (name "/R0A") (class "Default")
      (node (ref "OK1") (pin "2") (pinfunction "A_2") (pintype "passive"))
      (node (ref "R49") (pin "2") (pinfunction "2_2") (pintype "passive"))
    )
    (net (code "84") (name "/R1A") (class "Default")
      (node (ref "OK3") (pin "2") (pinfunction "A_2") (pintype "passive"))
      (node (ref "R27") (pin "2") (pinfunction "2_2") (pintype "passive"))
    )
    (net (code "85") (name "/R2") (class "Default")
      (node (ref "IC3") (pin "1") (pinfunction "R_1") (pintype "input"))
      (node (ref "OK5") (pin "3") (pinfunction "C_3") (pintype "passive"))
    )
    (net (code "86") (name "/R2A") (class "Default")
      (node (ref "OK5") (pin "2") (pinfunction "A_2") (pintype "passive"))
      (node (ref "R30") (pin "2") (pinfunction "2_2") (pintype "passive"))
    )
    (net (code "87") (name "/R3") (class "Default")
      (node (ref "IC4") (pin "1") (pinfunction "R_1") (pintype "input"))
      (node (ref "OK7") (pin "3") (pinfunction "C_3") (pintype "passive"))
    )
    (net (code "88") (name "/R3A") (class "Default")
      (node (ref "OK7") (pin "2") (pinfunction "A_2") (pintype "passive"))
      (node (ref "R31") (pin "2") (pinfunction "2_2") (pintype "passive"))
    )
    (net (code "89") (name "/RESET") (class "Default")
      (node (ref "U$1") (pin "P2") (pinfunction "P2_P2") (pintype "bidirectional"))
      (node (ref "U1") (pin "57") (pinfunction "~{RESET}/PDI_57") (pintype "bidirectional"))
    )
    (net (code "90") (name "/S0A") (class "Default")
      (node (ref "D1") (pin "3") (pinfunction "C2_3") (pintype "passive"))
      (node (ref "R1") (pin "1") (pinfunction "1_1") (pintype "passive"))
      (node (ref "R3") (pin "2") (pinfunction "2_2") (pintype "passive"))
    )
    (net (code "91") (name "/S0B") (class "Default")
      (node (ref "D1") (pin "2") (pinfunction "C1_2") (pintype "passive"))
      (node (ref "R2") (pin "1") (pinfunction "1_1") (pintype "passive"))
      (node (ref "R4") (pin "2") (pinfunction "2_2") (pintype "passive"))
    )
    (net (code "92") (name "/S1A") (class "Default")
      (node (ref "D2") (pin "3") (pinfunction "C2_3") (pintype "passive"))
      (node (ref "R13") (pin "2") (pinfunction "2_2") (pintype "passive"))
      (node (ref "R20") (pin "1") (pinfunction "1_1") (pintype "passive"))
    )
    (net (code "93") (name "/S1B") (class "Default")
      (node (ref "D2") (pin "2") (pinfunction "C1_2") (pintype "passive"))
      (node (ref "R14") (pin "2") (pinfunction "2_2") (pintype "passive"))
      (node (ref "R19") (pin "1") (pinfunction "1_1") (pintype "passive"))
    )
    (net (code "94") (name "/S2A") (class "Default")
      (node (ref "D3") (pin "3") (pinfunction "C2_3") (pintype "passive"))
      (node (ref "R15") (pin "2") (pinfunction "2_2") (pintype "passive"))
      (node (ref "R22") (pin "1") (pinfunction "1_1") (pintype "passive"))
    )
    (net (code "95") (name "/S2B") (class "Default")
      (node (ref "D3") (pin "2") (pinfunction "C1_2") (pintype "passive"))
      (node (ref "R16") (pin "2") (pinfunction "2_2") (pintype "passive"))
      (node (ref "R21") (pin "1") (pinfunction "1_1") (pintype "passive"))
    )
    (net (code "96") (name "/S3A") (class "Default")
      (node (ref "D4") (pin "3") (pinfunction "C2_3") (pintype "passive"))
      (node (ref "R17") (pin "2") (pinfunction "2_2") (pintype "passive"))
      (node (ref "R24") (pin "1") (pinfunction "1_1") (pintype "passive"))
    )
    (net (code "97") (name "/S3B") (class "Default")
      (node (ref "D4") (pin "2") (pinfunction "C1_2") (pintype "passive"))
      (node (ref "R18") (pin "2") (pinfunction "2_2") (pintype "passive"))
      (node (ref "R23") (pin "1") (pinfunction "1_1") (pintype "passive"))
    )
    (net (code "98") (name "/T0A") (class "Default")
      (node (ref "IC1") (pin "6") (pinfunction "A_6") (pintype "output"))
      (node (ref "R3") (pin "1") (pinfunction "1_1") (pintype "passive"))
      (node (ref "R5") (pin "2") (pinfunction "2_2") (pintype "passive"))
    )
    (net (code "99") (name "/T0B") (class "Default")
      (node (ref "IC1") (pin "7") (pinfunction "B_7") (pintype "output"))
      (node (ref "R4") (pin "1") (pinfunction "1_1") (pintype "passive"))
      (node (ref "R6") (pin "2") (pinfunction "2_2") (pintype "passive"))
    )
    (net (code "100") (name "/T1A") (class "Default")
      (node (ref "IC2") (pin "6") (pinfunction "A_6") (pintype "output"))
      (node (ref "R13") (pin "1") (pinfunction "1_1") (pintype "passive"))
      (node (ref "R7") (pin "2") (pinfunction "2_2") (pintype "passive"))
    )
    (net (code "101") (name "/T1B") (class "Default")
      (node (ref "IC2") (pin "7") (pinfunction "B_7") (pintype "output"))
      (node (ref "R14") (pin "1") (pinfunction "1_1") (pintype "passive"))
      (node (ref "R8") (pin "2") (pinfunction "2_2") (pintype "passive"))
    )
    (net (code "102") (name "/T2A") (class "Default")
      (node (ref "IC3") (pin "6") (pinfunction "A_6") (pintype "output"))
      (node (ref "R15") (pin "1") (pinfunction "1_1") (pintype "passive"))
      (node (ref "R9") (pin "2") (pinfunction "2_2") (pintype "passive"))
    )
    (net (code "103") (name "/T2B") (class "Default")
      (node (ref "IC3") (pin "7") (pinfunction "B_7") (pintype "output"))
      (node (ref "R10") (pin "2") (pinfunction "2_2") (pintype "passive"))
      (node (ref "R16") (pin "1") (pinfunction "1_1") (pintype "passive"))
    )
    (net (code "104") (name "/T3A") (class "Default")
      (node (ref "IC4") (pin "6") (pinfunction "A_6") (pintype "output"))
      (node (ref "R11") (pin "2") (pinfunction "2_2") (pintype "passive"))
      (node (ref "R17") (pin "1") (pinfunction "1_1") (pintype "passive"))
    )
    (net (code "105") (name "/T3B") (class "Default")
      (node (ref "IC4") (pin "7") (pinfunction "B_7") (pintype "output"))
      (node (ref "R12") (pin "2") (pinfunction "2_2") (pintype "passive"))
      (node (ref "R18") (pin "1") (pinfunction "1_1") (pintype "passive"))
    )
    (net (code "106") (name "/VCC") (class "Default")
      (node (ref "C10") (pin "2") (pinfunction "2_2") (pintype "passive"))
      (node (ref "C11") (pin "2") (pinfunction "2_2") (pintype "passive"))
      (node (ref "C12") (pin "2") (pinfunction "2_2") (pintype "passive"))
      (node (ref "C3") (pin "1") (pinfunction "1_1") (pintype "passive"))
      (node (ref "C4") (pin "1") (pinfunction "1_1") (pintype "passive"))
      (node (ref "C5") (pin "1") (pinfunction "1_1") (pintype "passive"))
      (node (ref "C6") (pin "1") (pinfunction "1_1") (pintype "passive"))
      (node (ref "C8") (pin "1") (pinfunction "1_1") (pintype "passive"))
      (node (ref "C9") (pin "2") (pinfunction "2_2") (pintype "passive"))
      (node (ref "IC5") (pin "3") (pinfunction "OUT_3") (pintype "passive"))
      (node (ref "OK1") (pin "8") (pinfunction "VCC_8") (pintype "passive"))
      (node (ref "OK3") (pin "8") (pinfunction "VCC_8") (pintype "passive"))
      (node (ref "OK5") (pin "8") (pinfunction "VCC_8") (pintype "passive"))
      (node (ref "OK7") (pin "8") (pinfunction "VCC_8") (pintype "passive"))
      (node (ref "R25") (pin "1") (pinfunction "1_1") (pintype "passive"))
      (node (ref "R26") (pin "1") (pinfunction "1_1") (pintype "passive"))
      (node (ref "R28") (pin "1") (pinfunction "1_1") (pintype "passive"))
      (node (ref "R29") (pin "1") (pinfunction "1_1") (pintype "passive"))
      (node (ref "SV1") (pin "1") (pinfunction "1_1") (pintype "passive"))
      (node (ref "SV1") (pin "11") (pinfunction "11_11") (pintype "passive"))
      (node (ref "SV2") (pin "1") (pinfunction "1_1") (pintype "passive"))
      (node (ref "SV2") (pin "11") (pinfunction "11_11") (pintype "passive"))
      (node (ref "SV3") (pin "1") (pinfunction "1_1") (pintype "passive"))
      (node (ref "SV3") (pin "11") (pinfunction "11_11") (pintype "passive"))
      (node (ref "SV4") (pin "1") (pinfunction "1_1") (pintype "passive"))
      (node (ref "SV4") (pin "11") (pinfunction "11_11") (pintype "passive"))
      (node (ref "SV5") (pin "1") (pinfunction "1_1") (pintype "passive"))
      (node (ref "SV5") (pin "11") (pinfunction "11_11") (pintype "passive"))
      (node (ref "SV6") (pin "1") (pinfunction "1_1") (pintype "passive"))
      (node (ref "SV6") (pin "11") (pinfunction "11_11") (pintype "passive"))
      (node (ref "U$2") (pin "P2") (pinfunction "P2_P2") (pintype "bidirectional"))
      (node (ref "U$3") (pin "P2") (pinfunction "P2_P2") (pintype "bidirectional"))
      (node (ref "U1") (pin "15") (pinfunction "VCC_15") (pintype "power_in"))
      (node (ref "U1") (pin "25") (pinfunction "VCC_25") (pintype "power_in"))
      (node (ref "U1") (pin "35") (pinfunction "VCC_35") (pintype "power_in"))
      (node (ref "U1") (pin "45") (pinfunction "VCC_45") (pintype "power_in"))
      (node (ref "U1") (pin "53") (pinfunction "VCC_53") (pintype "power_in"))
      (node (ref "U1") (pin "61") (pinfunction "AVCC_61") (pintype "power_in"))
    )
    (net (code "107") (name "/VIN") (class "Default")
      (node (ref "IC5") (pin "2") (pinfunction "IN_2") (pintype "input"))
      (node (ref "U$4") (pin "P2") (pinfunction "P2_P2") (pintype "bidirectional"))
      (node (ref "X2") (pin "9") (pinfunction "KL_9") (pintype "passive"))
    )
    (net (code "108") (name "/XTAL1") (class "Default")
      (node (ref "C1") (pin "2") (pinfunction "2_2") (pintype "passive"))
      (node (ref "Q1") (pin "1") (pinfunction "1_1") (pintype "passive"))
      (node (ref "U1") (pin "58") (pinfunction "PR0_58") (pintype "bidirectional"))
    )
    (net (code "109") (name "/XTAL2") (class "Default")
      (node (ref "C2") (pin "2") (pinfunction "2_2") (pintype "passive"))
      (node (ref "Q1") (pin "2") (pinfunction "2_2") (pintype "passive"))
      (node (ref "U1") (pin "59") (pinfunction "PR1_59") (pintype "bidirectional"))
    )
    (net (code "110") (name "Net-(IC1-R)") (class "Default")
      (node (ref "IC1") (pin "1") (pinfunction "R_1") (pintype "input"))
      (node (ref "OK1") (pin "3") (pinfunction "C_3") (pintype "passive"))
    )
    (net (code "111") (name "Net-(IC2-R)") (class "Default")
      (node (ref "IC2") (pin "1") (pinfunction "R_1") (pintype "input"))
      (node (ref "OK3") (pin "3") (pinfunction "C_3") (pintype "passive"))
    )
    (net (code "112") (name "Net-(OK2A-A1)") (class "Default")
      (node (ref "OK2") (pin "1") (pinfunction "A1_1") (pintype "passive"))
      (node (ref "R35") (pin "1") (pinfunction "1_1") (pintype "passive"))
    )
    (net (code "113") (name "Net-(OK2B-A2)") (class "Default")
      (node (ref "OK2") (pin "4") (pinfunction "A2_4") (pintype "passive"))
      (node (ref "R36") (pin "2") (pinfunction "2_2") (pintype "passive"))
    )
    (net (code "114") (name "Net-(OK4A-A1)") (class "Default")
      (node (ref "OK4") (pin "1") (pinfunction "A1_1") (pintype "passive"))
      (node (ref "R37") (pin "1") (pinfunction "1_1") (pintype "passive"))
    )
    (net (code "115") (name "Net-(OK4B-A2)") (class "Default")
      (node (ref "OK4") (pin "4") (pinfunction "A2_4") (pintype "passive"))
      (node (ref "R38") (pin "2") (pinfunction "2_2") (pintype "passive"))
    )
    (net (code "116") (name "Net-(OK6A-A1)") (class "Default")
      (node (ref "OK6") (pin "1") (pinfunction "A1_1") (pintype "passive"))
      (node (ref "R39") (pin "1") (pinfunction "1_1") (pintype "passive"))
    )
    (net (code "117") (name "Net-(OK6B-A2)") (class "Default")
      (node (ref "OK6") (pin "4") (pinfunction "A2_4") (pintype "passive"))
      (node (ref "R32") (pin "2") (pinfunction "2_2") (pintype "passive"))
    )
    (net (code "118") (name "Net-(OK9A-A1)") (class "Default")
      (node (ref "OK9") (pin "1") (pinfunction "A1_1") (pintype "passive"))
      (node (ref "R33") (pin "1") (pinfunction "1_1") (pintype "passive"))
    )
    (net (code "119") (name "Net-(OK9B-A2)") (class "Default")
      (node (ref "OK9") (pin "4") (pinfunction "A2_4") (pintype "passive"))
      (node (ref "R34") (pin "2") (pinfunction "2_2") (pintype "passive"))
    )
    (net (code "120") (name "unconnected-(OK1-VE-Pad7)") (class "Default")
      (node (ref "OK1") (pin "7") (pinfunction "VE_7") (pintype "passive"))
    )
    (net (code "121") (name "unconnected-(OK3-VE-Pad7)") (class "Default")
      (node (ref "OK3") (pin "7") (pinfunction "VE_7") (pintype "passive"))
    )
    (net (code "122") (name "unconnected-(OK5-VE-Pad7)") (class "Default")
      (node (ref "OK5") (pin "7") (pinfunction "VE_7") (pintype "passive"))
    )
    (net (code "123") (name "unconnected-(OK7-VE-Pad7)") (class "Default")
      (node (ref "OK7") (pin "7") (pinfunction "VE_7") (pintype "passive"))
    )
  )
)
